# LogicBoard.net
KiCad netlist of a schematic drawn in EAGLE
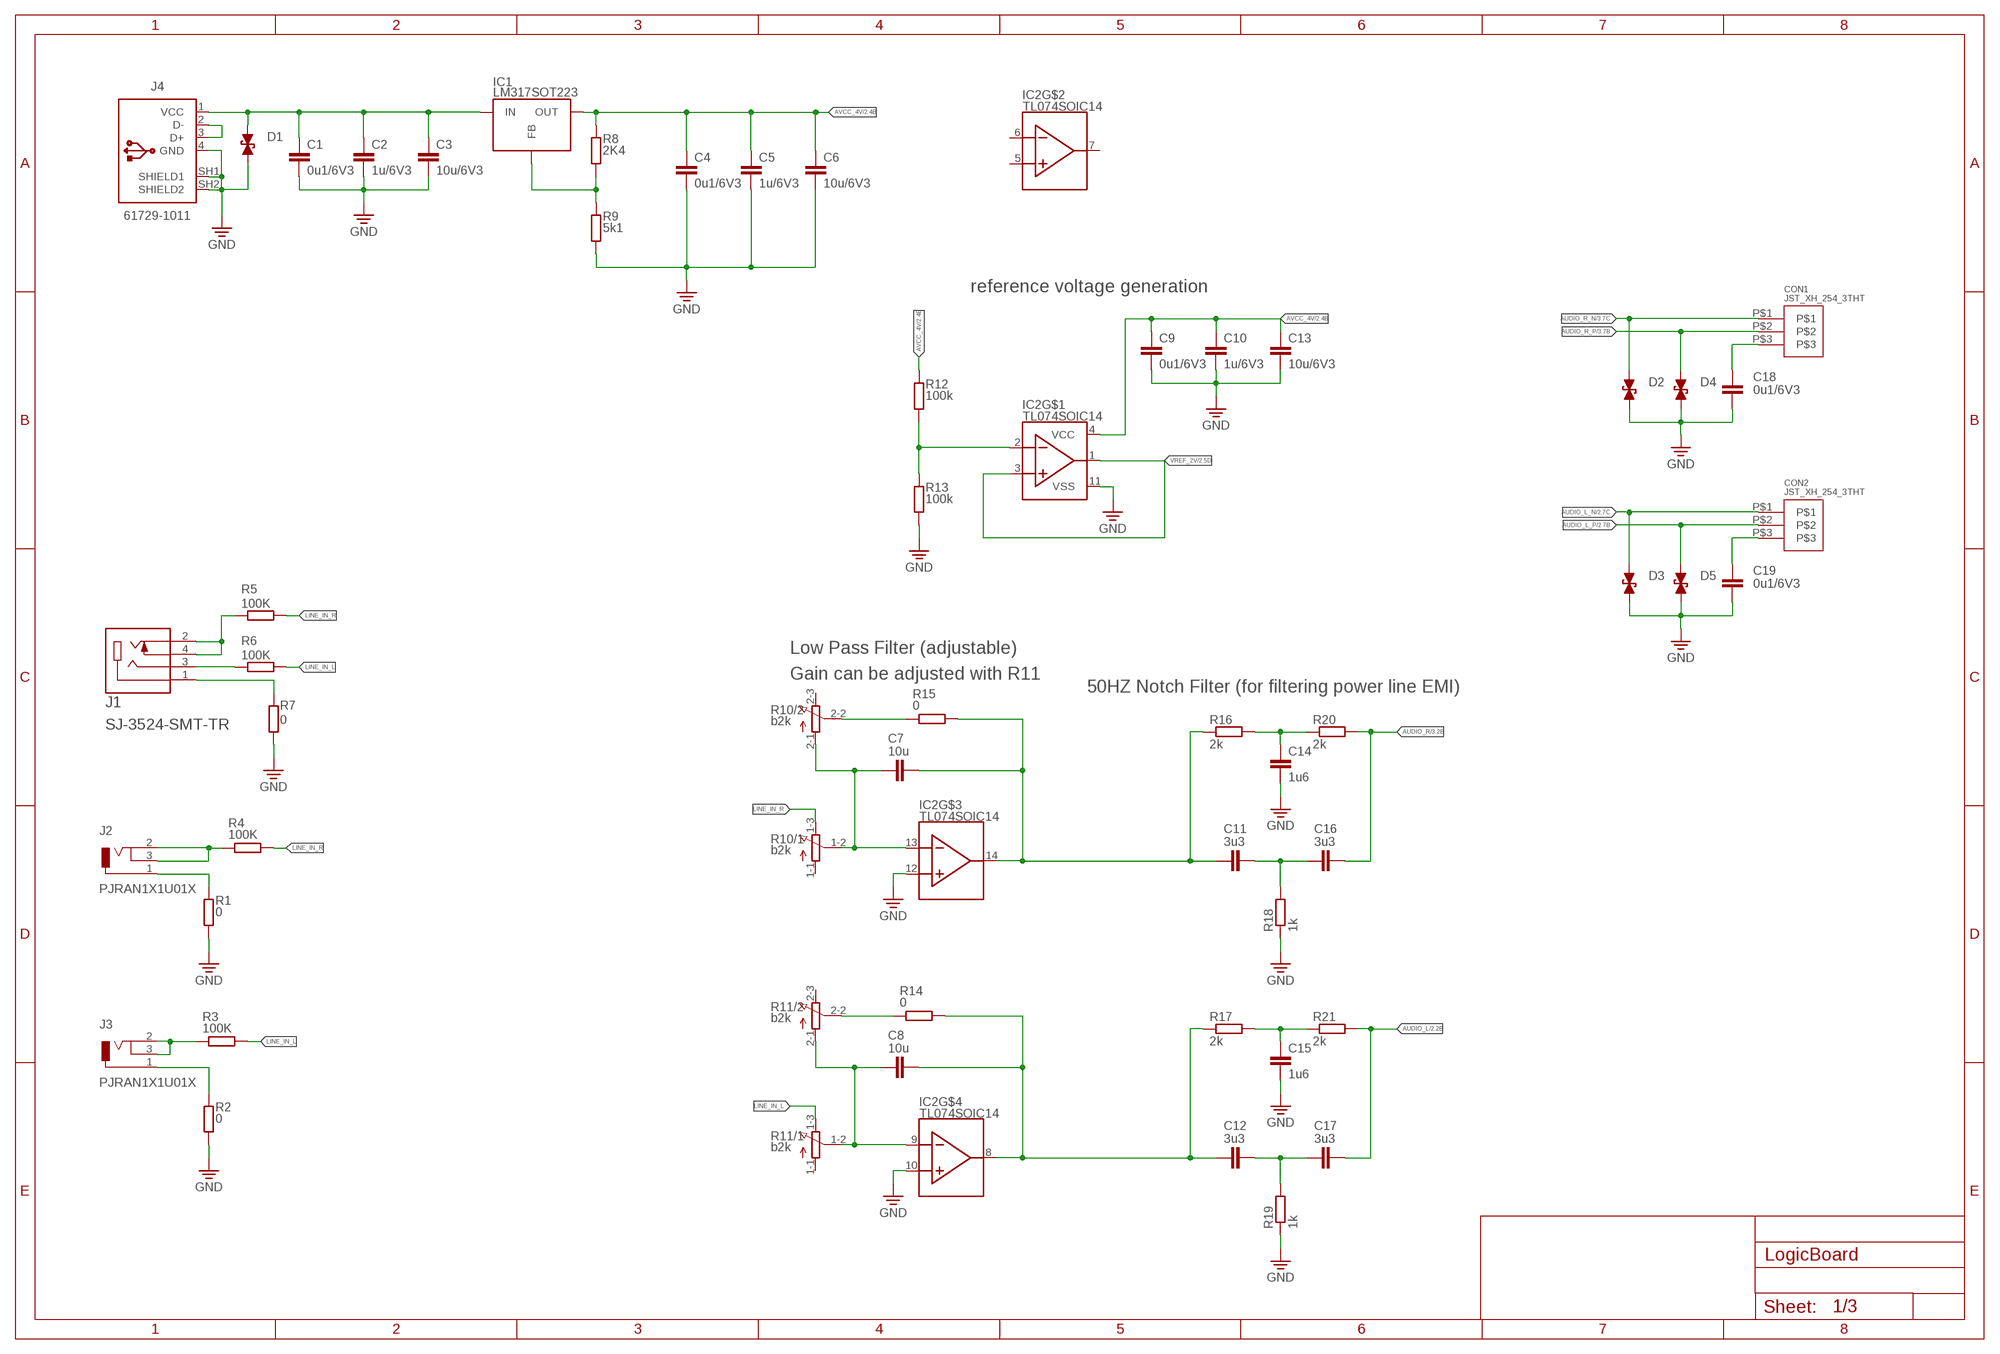
[diagram p0: schematic, sheet 1]
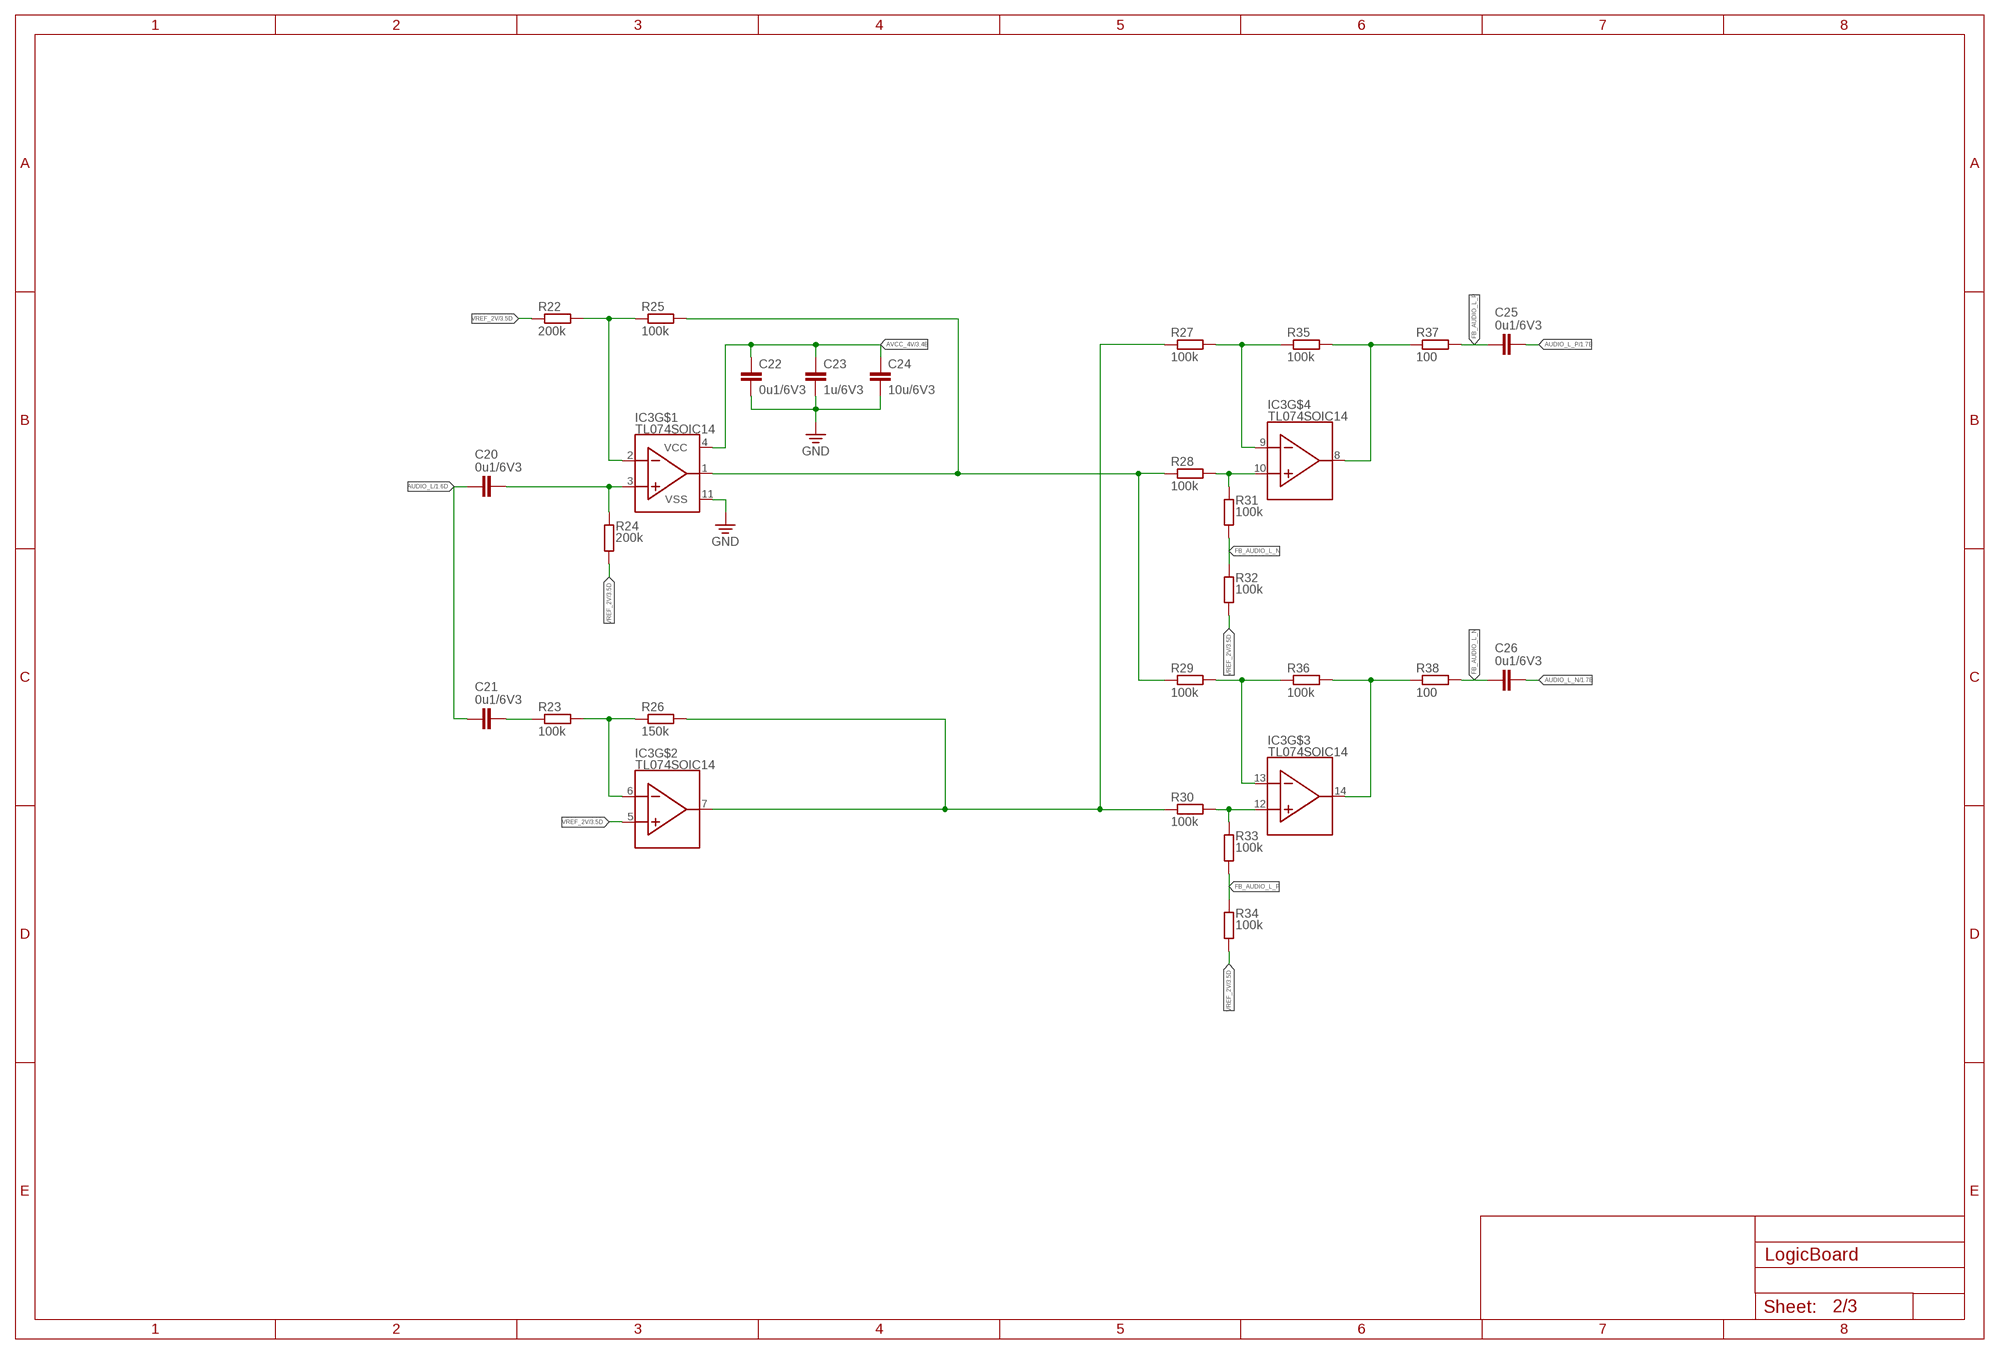
[diagram p1: schematic, sheet 2]
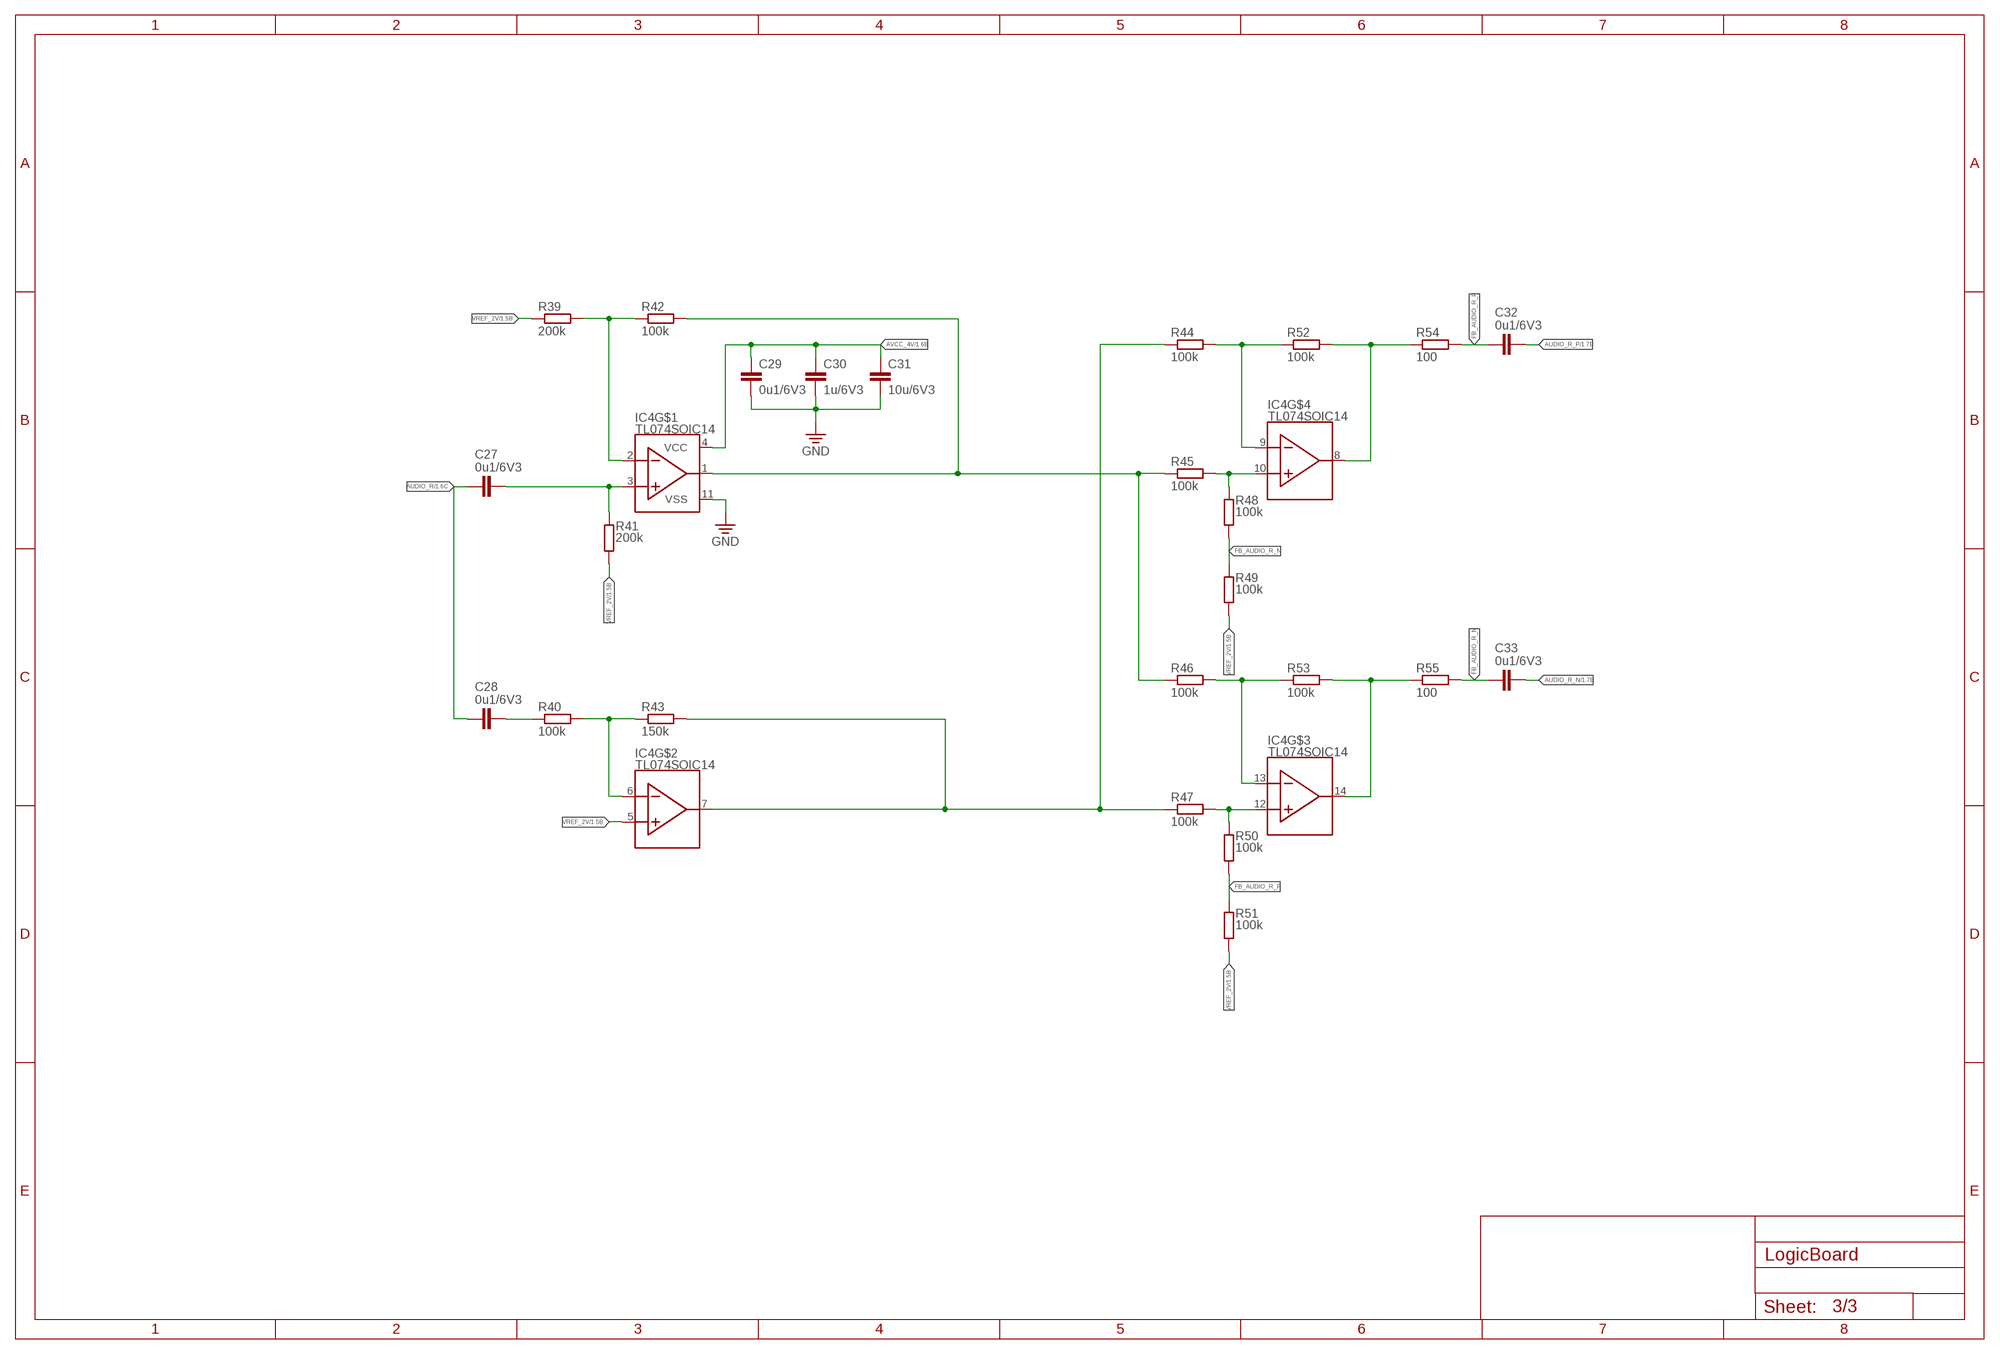
[diagram p2: schematic, sheet 3]

(export (version "E")
  (design (tool "Eeschema 10.0.6"))
  (components
    (comp (ref "C1")
      (value "0u1/6V3")
      (footprint "eagle-import:C1206")
      (libsource (lib "eagle-import") (part "C-EUC1206"))
    )
    (comp (ref "C2")
      (value "1u/6V3")
      (footprint "eagle-import:C1206")
      (libsource (lib "eagle-import") (part "C-EUC1206"))
    )
    (comp (ref "C3")
      (value "10u/6V3")
      (footprint "eagle-import:C1206")
      (libsource (lib "eagle-import") (part "C-EUC1206"))
    )
    (comp (ref "C4")
      (value "0u1/6V3")
      (footprint "eagle-import:C1206")
      (libsource (lib "eagle-import") (part "C-EUC1206"))
    )
    (comp (ref "C5")
      (value "1u/6V3")
      (footprint "eagle-import:C1206")
      (libsource (lib "eagle-import") (part "C-EUC1206"))
    )
    (comp (ref "C6")
      (value "10u/6V3")
      (footprint "eagle-import:C1206")
      (libsource (lib "eagle-import") (part "C-EUC1206"))
    )
    (comp (ref "C7")
      (value "10u")
      (footprint "eagle-import:C1206")
      (libsource (lib "eagle-import") (part "C-EUC1206"))
    )
    (comp (ref "C8")
      (value "10u")
      (footprint "eagle-import:C1206")
      (libsource (lib "eagle-import") (part "C-EUC1206"))
    )
    (comp (ref "C9")
      (value "0u1/6V3")
      (footprint "eagle-import:C1206")
      (libsource (lib "eagle-import") (part "C-EUC1206"))
    )
    (comp (ref "C10")
      (value "1u/6V3")
      (footprint "eagle-import:C1206")
      (libsource (lib "eagle-import") (part "C-EUC1206"))
    )
    (comp (ref "C11")
      (value "3u3")
      (footprint "eagle-import:C1206")
      (libsource (lib "eagle-import") (part "C-EUC1206"))
    )
    (comp (ref "C12")
      (value "3u3")
      (footprint "eagle-import:C1206")
      (libsource (lib "eagle-import") (part "C-EUC1206"))
    )
    (comp (ref "C13")
      (value "10u/6V3")
      (footprint "eagle-import:C1206")
      (libsource (lib "eagle-import") (part "C-EUC1206"))
    )
    (comp (ref "C14")
      (value "1u6")
      (footprint "eagle-import:C1206")
      (libsource (lib "eagle-import") (part "C-EUC1206"))
    )
    (comp (ref "C15")
      (value "1u6")
      (footprint "eagle-import:C1206")
      (libsource (lib "eagle-import") (part "C-EUC1206"))
    )
    (comp (ref "C16")
      (value "3u3")
      (footprint "eagle-import:C1206")
      (libsource (lib "eagle-import") (part "C-EUC1206"))
    )
    (comp (ref "C17")
      (value "3u3")
      (footprint "eagle-import:C1206")
      (libsource (lib "eagle-import") (part "C-EUC1206"))
    )
    (comp (ref "C18")
      (value "0u1/6V3")
      (footprint "eagle-import:C1206")
      (libsource (lib "eagle-import") (part "C-EUC1206"))
    )
    (comp (ref "C19")
      (value "0u1/6V3")
      (footprint "eagle-import:C1206")
      (libsource (lib "eagle-import") (part "C-EUC1206"))
    )
    (comp (ref "CON1")
      (value "JST_XH_254_3THT")
      (footprint "eagle-import:JST_XH_254_3_THT")
      (libsource (lib "eagle-import") (part "JST_XH_254_3THT"))
    )
    (comp (ref "CON2")
      (value "JST_XH_254_3THT")
      (footprint "eagle-import:JST_XH_254_3_THT")
      (libsource (lib "eagle-import") (part "JST_XH_254_3THT"))
    )
    (comp (ref "D1")
      (value "DIODE_PGB-0603MP")
      (footprint "eagle-import:DIODE_PGB-0603MP")
      (libsource (lib "eagle-import") (part "DIODE_PGB-0603MP"))
    )
    (comp (ref "D2")
      (value "DIODE_PGB-0603MP")
      (footprint "eagle-import:DIODE_PGB-0603MP")
      (libsource (lib "eagle-import") (part "DIODE_PGB-0603MP"))
    )
    (comp (ref "D3")
      (value "DIODE_PGB-0603MP")
      (footprint "eagle-import:DIODE_PGB-0603MP")
      (libsource (lib "eagle-import") (part "DIODE_PGB-0603MP"))
    )
    (comp (ref "D4")
      (value "DIODE_PGB-0603MP")
      (footprint "eagle-import:DIODE_PGB-0603MP")
      (libsource (lib "eagle-import") (part "DIODE_PGB-0603MP"))
    )
    (comp (ref "D5")
      (value "DIODE_PGB-0603MP")
      (footprint "eagle-import:DIODE_PGB-0603MP")
      (libsource (lib "eagle-import") (part "DIODE_PGB-0603MP"))
    )
    (comp (ref "IC1")
      (value "LM317SOT223")
      (footprint "eagle-import:SOT230P700X180-4N")
      (libsource (lib "eagle-import") (part "LM317SOT223"))
    )
    (comp (ref "IC2")
      (value "TL074SOIC14")
      (footprint "eagle-import:SOIC127P600X175-14N")
      (libsource (lib "eagle-import") (part "TL074SOIC14"))
    )
    (comp (ref "J1")
      (value "SJ-3524-SMT-TR")
      (footprint "eagle-import:SJ-3524-SMT-TR")
      (fields (field (name "DIGIKEY_PARTNO") "CP-3524SJTR-ND") (field (name "CREATED_BY") "PCBLayout.com"))
      (libsource (lib "eagle-import") (part "SJ-3524-SMT-TR"))
    )
    (comp (ref "J2")
      (value "PJRAN1X1U01X")
      (footprint "eagle-import:PJRAN1X1U01X")
      (fields
        (field (name "DIGIKEY_PART_NUMBER") "PJRAN1X1U01X-ND")
        (field (name "MANUFACTURER") "Switchcraft Inc.")
        (field (name "CREATED_BY") "PCBLayout.com")
      )
      (libsource (lib "eagle-import") (part "PJRAN1X1U01X"))
    )
    (comp (ref "J3")
      (value "PJRAN1X1U01X")
      (footprint "eagle-import:PJRAN1X1U01X")
      (fields
        (field (name "DIGIKEY_PART_NUMBER") "PJRAN1X1U01X-ND")
        (field (name "MANUFACTURER") "Switchcraft Inc.")
        (field (name "CREATED_BY") "PCBLayout.com")
      )
      (libsource (lib "eagle-import") (part "PJRAN1X1U01X"))
    )
    (comp (ref "J4")
      (value "61729-1011")
      (footprint "eagle-import:61729-1011BLF")
      (fields (field (name "MANUFACTURER") "Amphenol ICC (FCI)") (field (name "MPN") "61729-1011BLF"))
      (libsource (lib "eagle-import") (part "61729-1011"))
    )
    (comp (ref "R1")
      (value "0")
      (footprint "eagle-import:R0603")
      (libsource (lib "eagle-import") (part "R-EU_R0603"))
    )
    (comp (ref "R2")
      (value "0")
      (footprint "eagle-import:R0603")
      (libsource (lib "eagle-import") (part "R-EU_R0603"))
    )
    (comp (ref "R3")
      (value "100K")
      (footprint "eagle-import:R0603")
      (libsource (lib "eagle-import") (part "R-EU_R0603"))
    )
    (comp (ref "R4")
      (value "100K")
      (footprint "eagle-import:R0603")
      (libsource (lib "eagle-import") (part "R-EU_R0603"))
    )
    (comp (ref "R5")
      (value "100K")
      (footprint "eagle-import:R0603")
      (libsource (lib "eagle-import") (part "R-EU_R0603"))
    )
    (comp (ref "R6")
      (value "100K")
      (footprint "eagle-import:R0603")
      (libsource (lib "eagle-import") (part "R-EU_R0603"))
    )
    (comp (ref "R7")
      (value "0")
      (footprint "eagle-import:R0603")
      (libsource (lib "eagle-import") (part "R-EU_R0603"))
    )
    (comp (ref "R8")
      (value "2K4")
      (footprint "eagle-import:R0603")
      (libsource (lib "eagle-import") (part "R-EU_R0603"))
    )
    (comp (ref "R9")
      (value "5k1")
      (footprint "eagle-import:R0603")
      (libsource (lib "eagle-import") (part "R-EU_R0603"))
    )
    (comp (ref "R10")
      (value "b2k")
      (footprint "eagle-import:3RP_1610G")
      (libsource (lib "eagle-import") (part "3RP/1610G"))
    )
    (comp (ref "R11")
      (value "b2k")
      (footprint "eagle-import:3RP_1610G")
      (libsource (lib "eagle-import") (part "3RP/1610G"))
    )
    (comp (ref "R12")
      (value "100k")
      (footprint "eagle-import:R0603")
      (libsource (lib "eagle-import") (part "R-EU_R0603"))
    )
    (comp (ref "R13")
      (value "100k")
      (footprint "eagle-import:R0603")
      (libsource (lib "eagle-import") (part "R-EU_R0603"))
    )
    (comp (ref "R14")
      (value "0")
      (footprint "eagle-import:R0603")
      (libsource (lib "eagle-import") (part "R-EU_R0603"))
    )
    (comp (ref "R15")
      (value "0")
      (footprint "eagle-import:R0603")
      (libsource (lib "eagle-import") (part "R-EU_R0603"))
    )
    (comp (ref "R16")
      (value "2k")
      (footprint "eagle-import:R0603")
      (libsource (lib "eagle-import") (part "R-EU_R0603"))
    )
    (comp (ref "R17")
      (value "2k")
      (footprint "eagle-import:R0603")
      (libsource (lib "eagle-import") (part "R-EU_R0603"))
    )
    (comp (ref "R18")
      (value "1k")
      (footprint "eagle-import:R0603")
      (libsource (lib "eagle-import") (part "R-EU_R0603"))
    )
    (comp (ref "R19")
      (value "1k")
      (footprint "eagle-import:R0603")
      (libsource (lib "eagle-import") (part "R-EU_R0603"))
    )
    (comp (ref "R20")
      (value "2k")
      (footprint "eagle-import:R0603")
      (libsource (lib "eagle-import") (part "R-EU_R0603"))
    )
    (comp (ref "R21")
      (value "2k")
      (footprint "eagle-import:R0603")
      (libsource (lib "eagle-import") (part "R-EU_R0603"))
    )
    (comp (ref "C27")
      (value "0u1/6V3")
      (footprint "eagle-import:C1206")
      (libsource (lib "eagle-import") (part "C-EUC1206"))
    )
    (comp (ref "C28")
      (value "0u1/6V3")
      (footprint "eagle-import:C1206")
      (libsource (lib "eagle-import") (part "C-EUC1206"))
    )
    (comp (ref "C29")
      (value "0u1/6V3")
      (footprint "eagle-import:C1206")
      (libsource (lib "eagle-import") (part "C-EUC1206"))
    )
    (comp (ref "C30")
      (value "1u/6V3")
      (footprint "eagle-import:C1206")
      (libsource (lib "eagle-import") (part "C-EUC1206"))
    )
    (comp (ref "C31")
      (value "10u/6V3")
      (footprint "eagle-import:C1206")
      (libsource (lib "eagle-import") (part "C-EUC1206"))
    )
    (comp (ref "C32")
      (value "0u1/6V3")
      (footprint "eagle-import:C1206")
      (libsource (lib "eagle-import") (part "C-EUC1206"))
    )
    (comp (ref "C33")
      (value "0u1/6V3")
      (footprint "eagle-import:C1206")
      (libsource (lib "eagle-import") (part "C-EUC1206"))
    )
    (comp (ref "IC4")
      (value "TL074SOIC14")
      (footprint "eagle-import:SOIC127P600X175-14N")
      (libsource (lib "eagle-import") (part "TL074SOIC14"))
    )
    (comp (ref "R39")
      (value "200k")
      (footprint "eagle-import:R0603")
      (libsource (lib "eagle-import") (part "R-EU_R0603"))
    )
    (comp (ref "R40")
      (value "100k")
      (footprint "eagle-import:R0603")
      (libsource (lib "eagle-import") (part "R-EU_R0603"))
    )
    (comp (ref "R41")
      (value "200k")
      (footprint "eagle-import:R0603")
      (libsource (lib "eagle-import") (part "R-EU_R0603"))
    )
    (comp (ref "R42")
      (value "100k")
      (footprint "eagle-import:R0603")
      (libsource (lib "eagle-import") (part "R-EU_R0603"))
    )
    (comp (ref "R43")
      (value "150k")
      (footprint "eagle-import:R0603")
      (libsource (lib "eagle-import") (part "R-EU_R0603"))
    )
    (comp (ref "R44")
      (value "100k")
      (footprint "eagle-import:R0603")
      (libsource (lib "eagle-import") (part "R-EU_R0603"))
    )
    (comp (ref "R45")
      (value "100k")
      (footprint "eagle-import:R0603")
      (libsource (lib "eagle-import") (part "R-EU_R0603"))
    )
    (comp (ref "R46")
      (value "100k")
      (footprint "eagle-import:R0603")
      (libsource (lib "eagle-import") (part "R-EU_R0603"))
    )
    (comp (ref "R47")
      (value "100k")
      (footprint "eagle-import:R0603")
      (libsource (lib "eagle-import") (part "R-EU_R0603"))
    )
    (comp (ref "R48")
      (value "100k")
      (footprint "eagle-import:R0603")
      (libsource (lib "eagle-import") (part "R-EU_R0603"))
    )
    (comp (ref "R49")
      (value "100k")
      (footprint "eagle-import:R0603")
      (libsource (lib "eagle-import") (part "R-EU_R0603"))
    )
    (comp (ref "R50")
      (value "100k")
      (footprint "eagle-import:R0603")
      (libsource (lib "eagle-import") (part "R-EU_R0603"))
    )
    (comp (ref "R51")
      (value "100k")
      (footprint "eagle-import:R0603")
      (libsource (lib "eagle-import") (part "R-EU_R0603"))
    )
    (comp (ref "R52")
      (value "100k")
      (footprint "eagle-import:R0603")
      (libsource (lib "eagle-import") (part "R-EU_R0603"))
    )
    (comp (ref "R53")
      (value "100k")
      (footprint "eagle-import:R0603")
      (libsource (lib "eagle-import") (part "R-EU_R0603"))
    )
    (comp (ref "R54")
      (value "100")
      (footprint "eagle-import:R0603")
      (libsource (lib "eagle-import") (part "R-EU_R0603"))
    )
    (comp (ref "R55")
      (value "100")
      (footprint "eagle-import:R0603")
      (libsource (lib "eagle-import") (part "R-EU_R0603"))
    )
    (comp (ref "C20")
      (value "0u1/6V3")
      (footprint "eagle-import:C1206")
      (libsource (lib "eagle-import") (part "C-EUC1206"))
    )
    (comp (ref "C21")
      (value "0u1/6V3")
      (footprint "eagle-import:C1206")
      (libsource (lib "eagle-import") (part "C-EUC1206"))
    )
    (comp (ref "C22")
      (value "0u1/6V3")
      (footprint "eagle-import:C1206")
      (libsource (lib "eagle-import") (part "C-EUC1206"))
    )
    (comp (ref "C23")
      (value "1u/6V3")
      (footprint "eagle-import:C1206")
      (libsource (lib "eagle-import") (part "C-EUC1206"))
    )
    (comp (ref "C24")
      (value "10u/6V3")
      (footprint "eagle-import:C1206")
      (libsource (lib "eagle-import") (part "C-EUC1206"))
    )
    (comp (ref "C25")
      (value "0u1/6V3")
      (footprint "eagle-import:C1206")
      (libsource (lib "eagle-import") (part "C-EUC1206"))
    )
    (comp (ref "C26")
      (value "0u1/6V3")
      (footprint "eagle-import:C1206")
      (libsource (lib "eagle-import") (part "C-EUC1206"))
    )
    (comp (ref "IC3")
      (value "TL074SOIC14")
      (footprint "eagle-import:SOIC127P600X175-14N")
      (libsource (lib "eagle-import") (part "TL074SOIC14"))
    )
    (comp (ref "R22")
      (value "200k")
      (footprint "eagle-import:R0603")
      (libsource (lib "eagle-import") (part "R-EU_R0603"))
    )
    (comp (ref "R23")
      (value "100k")
      (footprint "eagle-import:R0603")
      (libsource (lib "eagle-import") (part "R-EU_R0603"))
    )
    (comp (ref "R24")
      (value "200k")
      (footprint "eagle-import:R0603")
      (libsource (lib "eagle-import") (part "R-EU_R0603"))
    )
    (comp (ref "R25")
      (value "100k")
      (footprint "eagle-import:R0603")
      (libsource (lib "eagle-import") (part "R-EU_R0603"))
    )
    (comp (ref "R26")
      (value "150k")
      (footprint "eagle-import:R0603")
      (libsource (lib "eagle-import") (part "R-EU_R0603"))
    )
    (comp (ref "R27")
      (value "100k")
      (footprint "eagle-import:R0603")
      (libsource (lib "eagle-import") (part "R-EU_R0603"))
    )
    (comp (ref "R28")
      (value "100k")
      (footprint "eagle-import:R0603")
      (libsource (lib "eagle-import") (part "R-EU_R0603"))
    )
    (comp (ref "R29")
      (value "100k")
      (footprint "eagle-import:R0603")
      (libsource (lib "eagle-import") (part "R-EU_R0603"))
    )
    (comp (ref "R30")
      (value "100k")
      (footprint "eagle-import:R0603")
      (libsource (lib "eagle-import") (part "R-EU_R0603"))
    )
    (comp (ref "R31")
      (value "100k")
      (footprint "eagle-import:R0603")
      (libsource (lib "eagle-import") (part "R-EU_R0603"))
    )
    (comp (ref "R32")
      (value "100k")
      (footprint "eagle-import:R0603")
      (libsource (lib "eagle-import") (part "R-EU_R0603"))
    )
    (comp (ref "R33")
      (value "100k")
      (footprint "eagle-import:R0603")
      (libsource (lib "eagle-import") (part "R-EU_R0603"))
    )
    (comp (ref "R34")
      (value "100k")
      (footprint "eagle-import:R0603")
      (libsource (lib "eagle-import") (part "R-EU_R0603"))
    )
    (comp (ref "R35")
      (value "100k")
      (footprint "eagle-import:R0603")
      (libsource (lib "eagle-import") (part "R-EU_R0603"))
    )
    (comp (ref "R36")
      (value "100k")
      (footprint "eagle-import:R0603")
      (libsource (lib "eagle-import") (part "R-EU_R0603"))
    )
    (comp (ref "R37")
      (value "100")
      (footprint "eagle-import:R0603")
      (libsource (lib "eagle-import") (part "R-EU_R0603"))
    )
    (comp (ref "R38")
      (value "100")
      (footprint "eagle-import:R0603")
      (libsource (lib "eagle-import") (part "R-EU_R0603"))
    )
  )
  (nets
    (net (code "1") (name "AUDIO_L") (class "Default")
      (node (ref "C17") (pin "2") (pinfunction "2_2") (pintype "passive"))
      (node (ref "C20") (pin "2") (pinfunction "2_2") (pintype "passive"))
      (node (ref "C21") (pin "2") (pinfunction "2_2") (pintype "passive"))
      (node (ref "R21") (pin "2") (pinfunction "2_2") (pintype "passive"))
    )
    (net (code "2") (name "AUDIO_L_N") (class "Default")
      (node (ref "C26") (pin "1") (pinfunction "1_1") (pintype "passive"))
      (node (ref "CON2") (pin "P$1") (pinfunction "P$1_P$1") (pintype "bidirectional"))
      (node (ref "D3") (pin "2") (pinfunction "2_2") (pintype "passive"))
    )
    (net (code "3") (name "AUDIO_L_P") (class "Default")
      (node (ref "C25") (pin "1") (pinfunction "1_1") (pintype "passive"))
      (node (ref "CON2") (pin "P$2") (pinfunction "P$2_P$2") (pintype "bidirectional"))
      (node (ref "D5") (pin "2") (pinfunction "2_2") (pintype "passive"))
    )
    (net (code "4") (name "AUDIO_R") (class "Default")
      (node (ref "C16") (pin "2") (pinfunction "2_2") (pintype "passive"))
      (node (ref "C27") (pin "2") (pinfunction "2_2") (pintype "passive"))
      (node (ref "C28") (pin "2") (pinfunction "2_2") (pintype "passive"))
      (node (ref "R20") (pin "2") (pinfunction "2_2") (pintype "passive"))
    )
    (net (code "5") (name "AUDIO_R_N") (class "Default")
      (node (ref "C33") (pin "1") (pinfunction "1_1") (pintype "passive"))
      (node (ref "CON1") (pin "P$1") (pinfunction "P$1_P$1") (pintype "bidirectional"))
      (node (ref "D2") (pin "2") (pinfunction "2_2") (pintype "passive"))
    )
    (net (code "6") (name "AUDIO_R_P") (class "Default")
      (node (ref "C32") (pin "1") (pinfunction "1_1") (pintype "passive"))
      (node (ref "CON1") (pin "P$2") (pinfunction "P$2_P$2") (pintype "bidirectional"))
      (node (ref "D4") (pin "2") (pinfunction "2_2") (pintype "passive"))
    )
    (net (code "7") (name "AVCC_4V") (class "Default")
      (node (ref "C10") (pin "1") (pinfunction "1_1") (pintype "passive"))
      (node (ref "C13") (pin "1") (pinfunction "1_1") (pintype "passive"))
      (node (ref "C22") (pin "1") (pinfunction "1_1") (pintype "passive"))
      (node (ref "C23") (pin "1") (pinfunction "1_1") (pintype "passive"))
      (node (ref "C24") (pin "1") (pinfunction "1_1") (pintype "passive"))
      (node (ref "C29") (pin "1") (pinfunction "1_1") (pintype "passive"))
      (node (ref "C30") (pin "1") (pinfunction "1_1") (pintype "passive"))
      (node (ref "C31") (pin "1") (pinfunction "1_1") (pintype "passive"))
      (node (ref "C4") (pin "1") (pinfunction "1_1") (pintype "passive"))
      (node (ref "C5") (pin "1") (pinfunction "1_1") (pintype "passive"))
      (node (ref "C6") (pin "1") (pinfunction "1_1") (pintype "passive"))
      (node (ref "C9") (pin "1") (pinfunction "1_1") (pintype "passive"))
      (node (ref "IC1") (pin "2") (pinfunction "OUT_2") (pintype "power_in"))
      (node (ref "IC2") (pin "4") (pinfunction "VCC_4") (pintype "power_in"))
      (node (ref "IC3") (pin "4") (pinfunction "VCC_4") (pintype "power_in"))
      (node (ref "IC4") (pin "4") (pinfunction "VCC_4") (pintype "power_in"))
      (node (ref "R12") (pin "2") (pinfunction "2_2") (pintype "passive"))
      (node (ref "R8") (pin "2") (pinfunction "2_2") (pintype "passive"))
    )
    (net (code "8") (name "FB_AUDIO_L_N") (class "Default")
      (node (ref "C26") (pin "2") (pinfunction "2_2") (pintype "passive"))
      (node (ref "R31") (pin "2") (pinfunction "2_2") (pintype "passive"))
      (node (ref "R32") (pin "1") (pinfunction "1_1") (pintype "passive"))
      (node (ref "R38") (pin "2") (pinfunction "2_2") (pintype "passive"))
    )
    (net (code "9") (name "FB_AUDIO_L_P") (class "Default")
      (node (ref "C25") (pin "2") (pinfunction "2_2") (pintype "passive"))
      (node (ref "R33") (pin "2") (pinfunction "2_2") (pintype "passive"))
      (node (ref "R34") (pin "1") (pinfunction "1_1") (pintype "passive"))
      (node (ref "R37") (pin "2") (pinfunction "2_2") (pintype "passive"))
    )
    (net (code "10") (name "FB_AUDIO_R_N") (class "Default")
      (node (ref "C33") (pin "2") (pinfunction "2_2") (pintype "passive"))
      (node (ref "R48") (pin "2") (pinfunction "2_2") (pintype "passive"))
      (node (ref "R49") (pin "1") (pinfunction "1_1") (pintype "passive"))
      (node (ref "R55") (pin "2") (pinfunction "2_2") (pintype "passive"))
    )
    (net (code "11") (name "FB_AUDIO_R_P") (class "Default")
      (node (ref "C32") (pin "2") (pinfunction "2_2") (pintype "passive"))
      (node (ref "R50") (pin "2") (pinfunction "2_2") (pintype "passive"))
      (node (ref "R51") (pin "1") (pinfunction "1_1") (pintype "passive"))
      (node (ref "R54") (pin "2") (pinfunction "2_2") (pintype "passive"))
    )
    (net (code "12") (name "GND") (class "Default")
      (node (ref "C1") (pin "2") (pinfunction "2_2") (pintype "passive"))
      (node (ref "C10") (pin "2") (pinfunction "2_2") (pintype "passive"))
      (node (ref "C13") (pin "2") (pinfunction "2_2") (pintype "passive"))
      (node (ref "C14") (pin "2") (pinfunction "2_2") (pintype "passive"))
      (node (ref "C15") (pin "2") (pinfunction "2_2") (pintype "passive"))
      (node (ref "C18") (pin "1") (pinfunction "1_1") (pintype "passive"))
      (node (ref "C19") (pin "1") (pinfunction "1_1") (pintype "passive"))
      (node (ref "C2") (pin "2") (pinfunction "2_2") (pintype "passive"))
      (node (ref "C22") (pin "2") (pinfunction "2_2") (pintype "passive"))
      (node (ref "C23") (pin "2") (pinfunction "2_2") (pintype "passive"))
      (node (ref "C24") (pin "2") (pinfunction "2_2") (pintype "passive"))
      (node (ref "C29") (pin "2") (pinfunction "2_2") (pintype "passive"))
      (node (ref "C3") (pin "2") (pinfunction "2_2") (pintype "passive"))
      (node (ref "C30") (pin "2") (pinfunction "2_2") (pintype "passive"))
      (node (ref "C31") (pin "2") (pinfunction "2_2") (pintype "passive"))
      (node (ref "C4") (pin "2") (pinfunction "2_2") (pintype "passive"))
      (node (ref "C5") (pin "2") (pinfunction "2_2") (pintype "passive"))
      (node (ref "C6") (pin "2") (pinfunction "2_2") (pintype "passive"))
      (node (ref "C9") (pin "2") (pinfunction "2_2") (pintype "passive"))
      (node (ref "D1") (pin "1") (pinfunction "1_1") (pintype "passive"))
      (node (ref "D2") (pin "1") (pinfunction "1_1") (pintype "passive"))
      (node (ref "D3") (pin "1") (pinfunction "1_1") (pintype "passive"))
      (node (ref "D4") (pin "1") (pinfunction "1_1") (pintype "passive"))
      (node (ref "D5") (pin "1") (pinfunction "1_1") (pintype "passive"))
      (node (ref "IC2") (pin "10") (pinfunction "IN+_10") (pintype "input"))
      (node (ref "IC2") (pin "11") (pinfunction "VSS_11") (pintype "power_in"))
      (node (ref "IC2") (pin "12") (pinfunction "IN+_12") (pintype "input"))
      (node (ref "IC3") (pin "11") (pinfunction "VSS_11") (pintype "power_in"))
      (node (ref "IC4") (pin "11") (pinfunction "VSS_11") (pintype "power_in"))
      (node (ref "J4") (pin "4") (pinfunction "GND_4") (pintype "power_in"))
      (node (ref "J4") (pin "SH1") (pinfunction "SHIELD1_SH1") (pintype "power_in"))
      (node (ref "J4") (pin "SH2") (pinfunction "SHIELD2_SH2") (pintype "power_in"))
      (node (ref "R1") (pin "2") (pinfunction "2_2") (pintype "passive"))
      (node (ref "R13") (pin "1") (pinfunction "1_1") (pintype "passive"))
      (node (ref "R18") (pin "1") (pinfunction "1_1") (pintype "passive"))
      (node (ref "R19") (pin "1") (pinfunction "1_1") (pintype "passive"))
      (node (ref "R2") (pin "2") (pinfunction "2_2") (pintype "passive"))
      (node (ref "R7") (pin "2") (pinfunction "2_2") (pintype "passive"))
      (node (ref "R9") (pin "1") (pinfunction "1_1") (pintype "passive"))
    )
    (net (code "13") (name "LINE_IN_L") (class "Default")
      (node (ref "R11") (pin "1-3") (pinfunction "E_1-3") (pintype "passive"))
      (node (ref "R3") (pin "2") (pinfunction "2_2") (pintype "passive"))
      (node (ref "R6") (pin "2") (pinfunction "2_2") (pintype "passive"))
    )
    (net (code "14") (name "LINE_IN_R") (class "Default")
      (node (ref "R10") (pin "1-3") (pinfunction "E_1-3") (pintype "passive"))
      (node (ref "R4") (pin "2") (pinfunction "2_2") (pintype "passive"))
      (node (ref "R5") (pin "2") (pinfunction "2_2") (pintype "passive"))
    )
    (net (code "15") (name "Net-(C11-Pad2)") (class "Default")
      (node (ref "C11") (pin "2") (pinfunction "2_2") (pintype "passive"))
      (node (ref "C16") (pin "1") (pinfunction "1_1") (pintype "passive"))
      (node (ref "R18") (pin "2") (pinfunction "2_2") (pintype "passive"))
    )
    (net (code "16") (name "Net-(C12-Pad2)") (class "Default")
      (node (ref "C12") (pin "2") (pinfunction "2_2") (pintype "passive"))
      (node (ref "C17") (pin "1") (pinfunction "1_1") (pintype "passive"))
      (node (ref "R19") (pin "2") (pinfunction "2_2") (pintype "passive"))
    )
    (net (code "17") (name "Net-(C14-Pad1)") (class "Default")
      (node (ref "C14") (pin "1") (pinfunction "1_1") (pintype "passive"))
      (node (ref "R16") (pin "2") (pinfunction "2_2") (pintype "passive"))
      (node (ref "R20") (pin "1") (pinfunction "1_1") (pintype "passive"))
    )
    (net (code "18") (name "Net-(C15-Pad1)") (class "Default")
      (node (ref "C15") (pin "1") (pinfunction "1_1") (pintype "passive"))
      (node (ref "R17") (pin "2") (pinfunction "2_2") (pintype "passive"))
      (node (ref "R21") (pin "1") (pinfunction "1_1") (pintype "passive"))
    )
    (net (code "19") (name "Net-(C18-Pad2)") (class "Default")
      (node (ref "C18") (pin "2") (pinfunction "2_2") (pintype "passive"))
      (node (ref "CON1") (pin "P$3") (pinfunction "P$3_P$3") (pintype "bidirectional"))
    )
    (net (code "20") (name "Net-(C19-Pad2)") (class "Default")
      (node (ref "C19") (pin "2") (pinfunction "2_2") (pintype "passive"))
      (node (ref "CON2") (pin "P$3") (pinfunction "P$3_P$3") (pintype "bidirectional"))
    )
    (net (code "21") (name "Net-(C21-Pad1)") (class "Default")
      (node (ref "C21") (pin "1") (pinfunction "1_1") (pintype "passive"))
      (node (ref "R23") (pin "1") (pinfunction "1_1") (pintype "passive"))
    )
    (net (code "22") (name "Net-(C28-Pad1)") (class "Default")
      (node (ref "C28") (pin "1") (pinfunction "1_1") (pintype "passive"))
      (node (ref "R40") (pin "1") (pinfunction "1_1") (pintype "passive"))
    )
    (net (code "23") (name "Net-(IC1-FB)") (class "Default")
      (node (ref "IC1") (pin "1") (pinfunction "FB_1") (pintype "input"))
      (node (ref "R8") (pin "1") (pinfunction "1_1") (pintype "passive"))
      (node (ref "R9") (pin "2") (pinfunction "2_2") (pintype "passive"))
    )
    (net (code "24") (name "Net-(IC1-IN)") (class "Default")
      (node (ref "C1") (pin "1") (pinfunction "1_1") (pintype "passive"))
      (node (ref "C2") (pin "1") (pinfunction "1_1") (pintype "passive"))
      (node (ref "C3") (pin "1") (pinfunction "1_1") (pintype "passive"))
      (node (ref "D1") (pin "2") (pinfunction "2_2") (pintype "passive"))
      (node (ref "IC1") (pin "3") (pinfunction "IN_3") (pintype "power_in"))
      (node (ref "J4") (pin "1") (pinfunction "VCC_1") (pintype "power_in"))
    )
    (net (code "25") (name "Net-(IC2A-IN-)") (class "Default")
      (node (ref "IC2") (pin "2") (pinfunction "IN-_2") (pintype "input"))
      (node (ref "R12") (pin "1") (pinfunction "1_1") (pintype "passive"))
      (node (ref "R13") (pin "2") (pinfunction "2_2") (pintype "passive"))
    )
    (net (code "26") (name "Net-(IC2C-IN-)") (class "Default")
      (node (ref "C7") (pin "1") (pinfunction "1_1") (pintype "passive"))
      (node (ref "IC2") (pin "13") (pinfunction "IN-_13") (pintype "input"))
      (node (ref "R10") (pin "1-2") (pinfunction "S_1-2") (pintype "passive"))
      (node (ref "R10") (pin "2-1") (pinfunction "A_2-1") (pintype "passive"))
    )
    (net (code "27") (name "Net-(IC2C-OUT)") (class "Default")
      (node (ref "C11") (pin "1") (pinfunction "1_1") (pintype "passive"))
      (node (ref "C7") (pin "2") (pinfunction "2_2") (pintype "passive"))
      (node (ref "IC2") (pin "14") (pinfunction "OUT_14") (pintype "output"))
      (node (ref "R15") (pin "2") (pinfunction "2_2") (pintype "passive"))
      (node (ref "R16") (pin "1") (pinfunction "1_1") (pintype "passive"))
    )
    (net (code "28") (name "Net-(IC2D-IN-)") (class "Default")
      (node (ref "C8") (pin "1") (pinfunction "1_1") (pintype "passive"))
      (node (ref "IC2") (pin "9") (pinfunction "IN-_9") (pintype "input"))
      (node (ref "R11") (pin "1-2") (pinfunction "S_1-2") (pintype "passive"))
      (node (ref "R11") (pin "2-1") (pinfunction "A_2-1") (pintype "passive"))
    )
    (net (code "29") (name "Net-(IC2D-OUT)") (class "Default")
      (node (ref "C12") (pin "1") (pinfunction "1_1") (pintype "passive"))
      (node (ref "C8") (pin "2") (pinfunction "2_2") (pintype "passive"))
      (node (ref "IC2") (pin "8") (pinfunction "OUT_8") (pintype "output"))
      (node (ref "R14") (pin "2") (pinfunction "2_2") (pintype "passive"))
      (node (ref "R17") (pin "1") (pinfunction "1_1") (pintype "passive"))
    )
    (net (code "30") (name "Net-(IC3A-IN+)") (class "Default")
      (node (ref "C20") (pin "1") (pinfunction "1_1") (pintype "passive"))
      (node (ref "IC3") (pin "3") (pinfunction "IN+_3") (pintype "input"))
      (node (ref "R24") (pin "2") (pinfunction "2_2") (pintype "passive"))
    )
    (net (code "31") (name "Net-(IC3A-IN-)") (class "Default")
      (node (ref "IC3") (pin "2") (pinfunction "IN-_2") (pintype "input"))
      (node (ref "R22") (pin "2") (pinfunction "2_2") (pintype "passive"))
      (node (ref "R25") (pin "1") (pinfunction "1_1") (pintype "passive"))
    )
    (net (code "32") (name "Net-(IC3A-OUT)") (class "Default")
      (node (ref "IC3") (pin "1") (pinfunction "OUT_1") (pintype "output"))
      (node (ref "R25") (pin "2") (pinfunction "2_2") (pintype "passive"))
      (node (ref "R28") (pin "1") (pinfunction "1_1") (pintype "passive"))
      (node (ref "R29") (pin "1") (pinfunction "1_1") (pintype "passive"))
    )
    (net (code "33") (name "Net-(IC3B-IN-)") (class "Default")
      (node (ref "IC3") (pin "6") (pinfunction "IN-_6") (pintype "input"))
      (node (ref "R23") (pin "2") (pinfunction "2_2") (pintype "passive"))
      (node (ref "R26") (pin "1") (pinfunction "1_1") (pintype "passive"))
    )
    (net (code "34") (name "Net-(IC3B-OUT)") (class "Default")
      (node (ref "IC3") (pin "7") (pinfunction "OUT_7") (pintype "output"))
      (node (ref "R26") (pin "2") (pinfunction "2_2") (pintype "passive"))
      (node (ref "R27") (pin "1") (pinfunction "1_1") (pintype "passive"))
      (node (ref "R30") (pin "1") (pinfunction "1_1") (pintype "passive"))
    )
    (net (code "35") (name "Net-(IC3C-IN+)") (class "Default")
      (node (ref "IC3") (pin "12") (pinfunction "IN+_12") (pintype "input"))
      (node (ref "R30") (pin "2") (pinfunction "2_2") (pintype "passive"))
      (node (ref "R33") (pin "1") (pinfunction "1_1") (pintype "passive"))
    )
    (net (code "36") (name "Net-(IC3C-IN-)") (class "Default")
      (node (ref "IC3") (pin "13") (pinfunction "IN-_13") (pintype "input"))
      (node (ref "R29") (pin "2") (pinfunction "2_2") (pintype "passive"))
      (node (ref "R36") (pin "1") (pinfunction "1_1") (pintype "passive"))
    )
    (net (code "37") (name "Net-(IC3C-OUT)") (class "Default")
      (node (ref "IC3") (pin "14") (pinfunction "OUT_14") (pintype "output"))
      (node (ref "R36") (pin "2") (pinfunction "2_2") (pintype "passive"))
      (node (ref "R38") (pin "1") (pinfunction "1_1") (pintype "passive"))
    )
    (net (code "38") (name "Net-(IC3D-IN+)") (class "Default")
      (node (ref "IC3") (pin "10") (pinfunction "IN+_10") (pintype "input"))
      (node (ref "R28") (pin "2") (pinfunction "2_2") (pintype "passive"))
      (node (ref "R31") (pin "1") (pinfunction "1_1") (pintype "passive"))
    )
    (net (code "39") (name "Net-(IC3D-IN-)") (class "Default")
      (node (ref "IC3") (pin "9") (pinfunction "IN-_9") (pintype "input"))
      (node (ref "R27") (pin "2") (pinfunction "2_2") (pintype "passive"))
      (node (ref "R35") (pin "1") (pinfunction "1_1") (pintype "passive"))
    )
    (net (code "40") (name "Net-(IC3D-OUT)") (class "Default")
      (node (ref "IC3") (pin "8") (pinfunction "OUT_8") (pintype "output"))
      (node (ref "R35") (pin "2") (pinfunction "2_2") (pintype "passive"))
      (node (ref "R37") (pin "1") (pinfunction "1_1") (pintype "passive"))
    )
    (net (code "41") (name "Net-(IC4A-IN+)") (class "Default")
      (node (ref "C27") (pin "1") (pinfunction "1_1") (pintype "passive"))
      (node (ref "IC4") (pin "3") (pinfunction "IN+_3") (pintype "input"))
      (node (ref "R41") (pin "2") (pinfunction "2_2") (pintype "passive"))
    )
    (net (code "42") (name "Net-(IC4A-IN-)") (class "Default")
      (node (ref "IC4") (pin "2") (pinfunction "IN-_2") (pintype "input"))
      (node (ref "R39") (pin "2") (pinfunction "2_2") (pintype "passive"))
      (node (ref "R42") (pin "1") (pinfunction "1_1") (pintype "passive"))
    )
    (net (code "43") (name "Net-(IC4A-OUT)") (class "Default")
      (node (ref "IC4") (pin "1") (pinfunction "OUT_1") (pintype "output"))
      (node (ref "R42") (pin "2") (pinfunction "2_2") (pintype "passive"))
      (node (ref "R45") (pin "1") (pinfunction "1_1") (pintype "passive"))
      (node (ref "R46") (pin "1") (pinfunction "1_1") (pintype "passive"))
    )
    (net (code "44") (name "Net-(IC4B-IN-)") (class "Default")
      (node (ref "IC4") (pin "6") (pinfunction "IN-_6") (pintype "input"))
      (node (ref "R40") (pin "2") (pinfunction "2_2") (pintype "passive"))
      (node (ref "R43") (pin "1") (pinfunction "1_1") (pintype "passive"))
    )
    (net (code "45") (name "Net-(IC4B-OUT)") (class "Default")
      (node (ref "IC4") (pin "7") (pinfunction "OUT_7") (pintype "output"))
      (node (ref "R43") (pin "2") (pinfunction "2_2") (pintype "passive"))
      (node (ref "R44") (pin "1") (pinfunction "1_1") (pintype "passive"))
      (node (ref "R47") (pin "1") (pinfunction "1_1") (pintype "passive"))
    )
    (net (code "46") (name "Net-(IC4C-IN+)") (class "Default")
      (node (ref "IC4") (pin "12") (pinfunction "IN+_12") (pintype "input"))
      (node (ref "R47") (pin "2") (pinfunction "2_2") (pintype "passive"))
      (node (ref "R50") (pin "1") (pinfunction "1_1") (pintype "passive"))
    )
    (net (code "47") (name "Net-(IC4C-IN-)") (class "Default")
      (node (ref "IC4") (pin "13") (pinfunction "IN-_13") (pintype "input"))
      (node (ref "R46") (pin "2") (pinfunction "2_2") (pintype "passive"))
      (node (ref "R53") (pin "1") (pinfunction "1_1") (pintype "passive"))
    )
    (net (code "48") (name "Net-(IC4C-OUT)") (class "Default")
      (node (ref "IC4") (pin "14") (pinfunction "OUT_14") (pintype "output"))
      (node (ref "R53") (pin "2") (pinfunction "2_2") (pintype "passive"))
      (node (ref "R55") (pin "1") (pinfunction "1_1") (pintype "passive"))
    )
    (net (code "49") (name "Net-(IC4D-IN+)") (class "Default")
      (node (ref "IC4") (pin "10") (pinfunction "IN+_10") (pintype "input"))
      (node (ref "R45") (pin "2") (pinfunction "2_2") (pintype "passive"))
      (node (ref "R48") (pin "1") (pinfunction "1_1") (pintype "passive"))
    )
    (net (code "50") (name "Net-(IC4D-IN-)") (class "Default")
      (node (ref "IC4") (pin "9") (pinfunction "IN-_9") (pintype "input"))
      (node (ref "R44") (pin "2") (pinfunction "2_2") (pintype "passive"))
      (node (ref "R52") (pin "1") (pinfunction "1_1") (pintype "passive"))
    )
    (net (code "51") (name "Net-(IC4D-OUT)") (class "Default")
      (node (ref "IC4") (pin "8") (pinfunction "OUT_8") (pintype "output"))
      (node (ref "R52") (pin "2") (pinfunction "2_2") (pintype "passive"))
      (node (ref "R54") (pin "1") (pinfunction "1_1") (pintype "passive"))
    )
    (net (code "52") (name "Net-(J1-Pad1)") (class "Default")
      (node (ref "J1") (pin "1") (pinfunction "1_1") (pintype "passive"))
      (node (ref "R7") (pin "1") (pinfunction "1_1") (pintype "passive"))
    )
    (net (code "53") (name "Net-(J1-Pad2)") (class "Default")
      (node (ref "J1") (pin "2") (pinfunction "2_2") (pintype "passive"))
      (node (ref "J1") (pin "4") (pinfunction "4_4") (pintype "passive"))
      (node (ref "R5") (pin "1") (pinfunction "1_1") (pintype "passive"))
    )
    (net (code "54") (name "Net-(J1-Pad3)") (class "Default")
      (node (ref "J1") (pin "3") (pinfunction "3_3") (pintype "passive"))
      (node (ref "R6") (pin "1") (pinfunction "1_1") (pintype "passive"))
    )
    (net (code "55") (name "Net-(J2-Pad1)") (class "Default")
      (node (ref "J2") (pin "1") (pinfunction "1_1") (pintype "passive"))
      (node (ref "R1") (pin "1") (pinfunction "1_1") (pintype "passive"))
    )
    (net (code "56") (name "Net-(J2-Pad2)") (class "Default")
      (node (ref "J2") (pin "2") (pinfunction "2_2") (pintype "passive"))
      (node (ref "J2") (pin "3") (pinfunction "3_3") (pintype "passive"))
      (node (ref "R4") (pin "1") (pinfunction "1_1") (pintype "passive"))
    )
    (net (code "57") (name "Net-(J3-Pad1)") (class "Default")
      (node (ref "J3") (pin "1") (pinfunction "1_1") (pintype "passive"))
      (node (ref "R2") (pin "1") (pinfunction "1_1") (pintype "passive"))
    )
    (net (code "58") (name "Net-(J3-Pad2)") (class "Default")
      (node (ref "J3") (pin "2") (pinfunction "2_2") (pintype "passive"))
      (node (ref "J3") (pin "3") (pinfunction "3_3") (pintype "passive"))
      (node (ref "R3") (pin "1") (pinfunction "1_1") (pintype "passive"))
    )
    (net (code "59") (name "Net-(J4-D+)") (class "Default")
      (node (ref "J4") (pin "2") (pinfunction "D-_2") (pintype "bidirectional"))
      (node (ref "J4") (pin "3") (pinfunction "D+_3") (pintype "bidirectional"))
    )
    (net (code "60") (name "Net-(R10B-S)") (class "Default")
      (node (ref "R10") (pin "2-2") (pinfunction "S_2-2") (pintype "passive"))
      (node (ref "R15") (pin "1") (pinfunction "1_1") (pintype "passive"))
    )
    (net (code "61") (name "Net-(R11B-S)") (class "Default")
      (node (ref "R11") (pin "2-2") (pinfunction "S_2-2") (pintype "passive"))
      (node (ref "R14") (pin "1") (pinfunction "1_1") (pintype "passive"))
    )
    (net (code "62") (name "VREF_2V") (class "Default")
      (node (ref "IC2") (pin "1") (pinfunction "OUT_1") (pintype "output"))
      (node (ref "IC2") (pin "3") (pinfunction "IN+_3") (pintype "input"))
      (node (ref "IC3") (pin "5") (pinfunction "IN+_5") (pintype "input"))
      (node (ref "IC4") (pin "5") (pinfunction "IN+_5") (pintype "input"))
      (node (ref "R22") (pin "1") (pinfunction "1_1") (pintype "passive"))
      (node (ref "R24") (pin "1") (pinfunction "1_1") (pintype "passive"))
      (node (ref "R32") (pin "2") (pinfunction "2_2") (pintype "passive"))
      (node (ref "R34") (pin "2") (pinfunction "2_2") (pintype "passive"))
      (node (ref "R39") (pin "1") (pinfunction "1_1") (pintype "passive"))
      (node (ref "R41") (pin "1") (pinfunction "1_1") (pintype "passive"))
      (node (ref "R49") (pin "2") (pinfunction "2_2") (pintype "passive"))
      (node (ref "R51") (pin "2") (pinfunction "2_2") (pintype "passive"))
    )
    (net (code "63") (name "unconnected-(IC2B-IN+-Pad5)") (class "Default")
      (node (ref "IC2") (pin "5") (pinfunction "IN+_5") (pintype "input"))
    )
    (net (code "64") (name "unconnected-(IC2B-IN--Pad6)") (class "Default")
      (node (ref "IC2") (pin "6") (pinfunction "IN-_6") (pintype "input"))
    )
    (net (code "65") (name "unconnected-(IC2B-OUT-Pad7)") (class "Default")
      (node (ref "IC2") (pin "7") (pinfunction "OUT_7") (pintype "output"))
    )
    (net (code "66") (name "unconnected-(R10A-A-Pad1-1)") (class "Default")
      (node (ref "R10") (pin "1-1") (pinfunction "A_1-1") (pintype "passive"))
    )
    (net (code "67") (name "unconnected-(R10B-E-Pad2-3)") (class "Default")
      (node (ref "R10") (pin "2-3") (pinfunction "E_2-3") (pintype "passive"))
    )
    (net (code "68") (name "unconnected-(R11A-A-Pad1-1)") (class "Default")
      (node (ref "R11") (pin "1-1") (pinfunction "A_1-1") (pintype "passive"))
    )
    (net (code "69") (name "unconnected-(R11B-E-Pad2-3)") (class "Default")
      (node (ref "R11") (pin "2-3") (pinfunction "E_2-3") (pintype "passive"))
    )
  )
)
